# main.net
KiCad netlist of a schematic drawn in Altium Designer
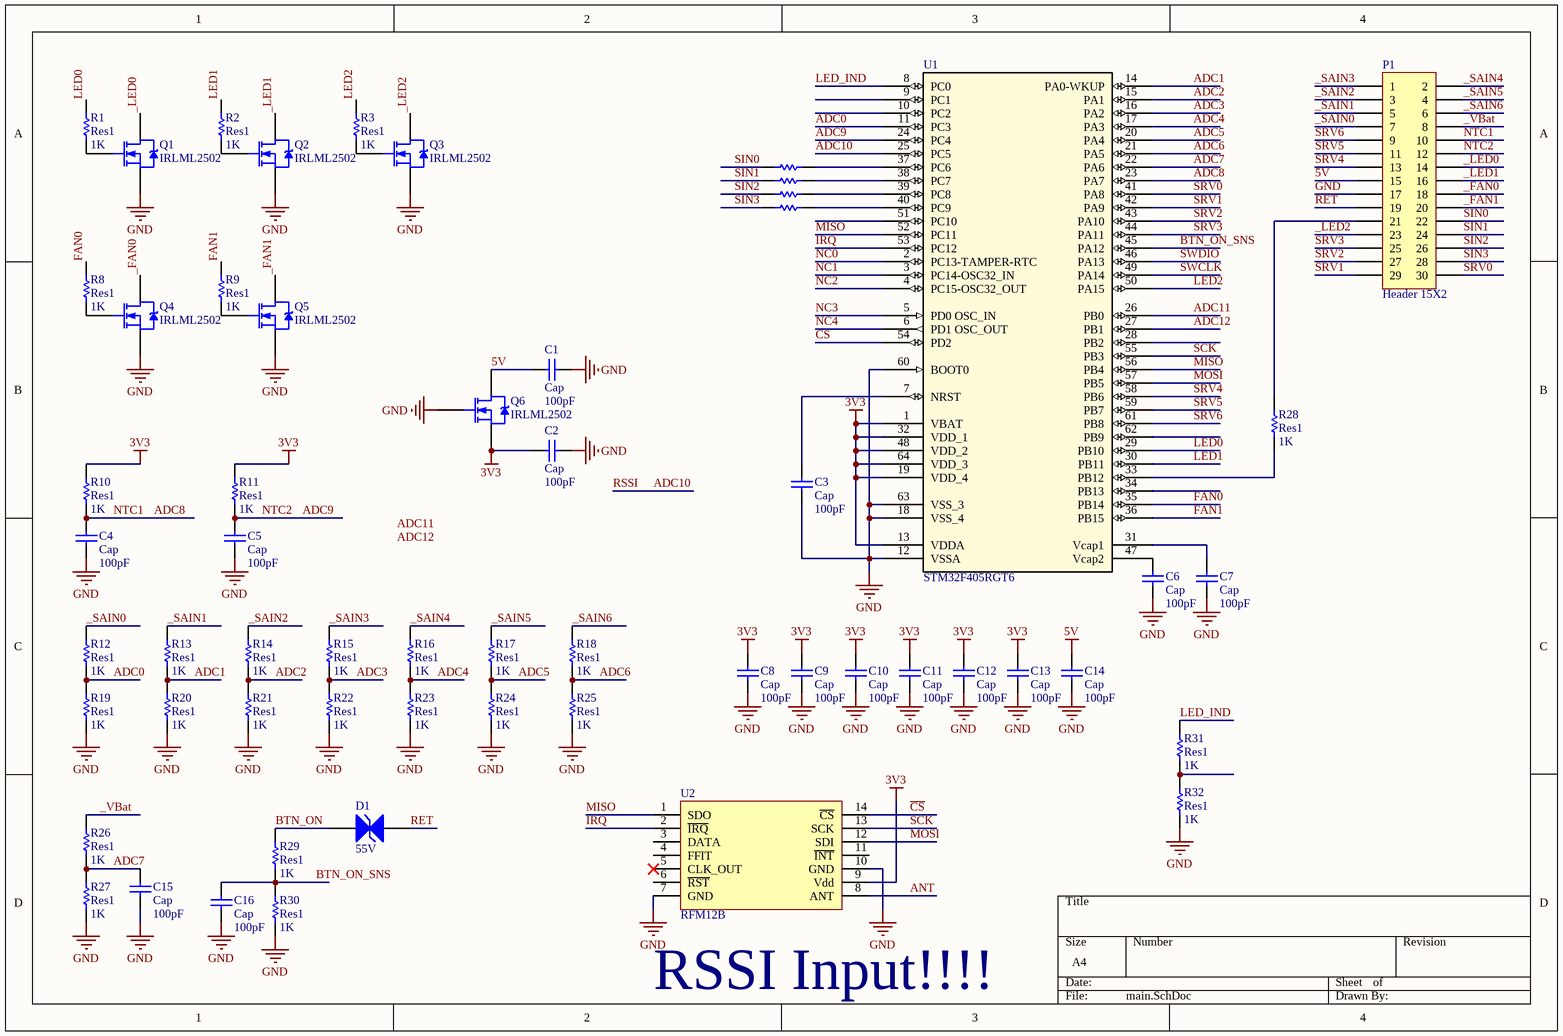
[diagram p0: main.SchDoc]

(export (version "E")
  (design (tool "Eeschema 10.0.6"))
  (components
    (comp (ref "C1")
      (value "Cap")
      (footprint "RC_1210_T1.8")
      (description "Capacitor")
      (fields (field (name "ALTIUM_VALUE") "100pF") (field (name "PUBLISHER") "Altium Limited"))
      (libsource (lib "Miscellaneous Devices") (part "Cap"))
    )
    (comp (ref "C2")
      (value "Cap")
      (footprint "RC_1210_T1.8")
      (description "Capacitor")
      (fields (field (name "ALTIUM_VALUE") "100pF") (field (name "PUBLISHER") "Altium Limited"))
      (libsource (lib "Miscellaneous Devices") (part "Cap"))
    )
    (comp (ref "C3")
      (value "Cap")
      (footprint "RC_0603")
      (description "Capacitor")
      (fields (field (name "ALTIUM_VALUE") "100pF") (field (name "PUBLISHER") "Altium Limited"))
      (libsource (lib "Miscellaneous Devices") (part "Cap"))
    )
    (comp (ref "C4")
      (value "Cap")
      (footprint "RC_0603")
      (description "Capacitor")
      (fields (field (name "ALTIUM_VALUE") "100pF") (field (name "PUBLISHER") "Altium Limited"))
      (libsource (lib "Miscellaneous Devices") (part "Cap"))
    )
    (comp (ref "C5")
      (value "Cap")
      (footprint "RC_0603")
      (description "Capacitor")
      (fields (field (name "ALTIUM_VALUE") "100pF") (field (name "PUBLISHER") "Altium Limited"))
      (libsource (lib "Miscellaneous Devices") (part "Cap"))
    )
    (comp (ref "C6")
      (value "Cap")
      (footprint "RC_0603")
      (description "Capacitor")
      (fields (field (name "ALTIUM_VALUE") "100pF") (field (name "PUBLISHER") "Altium Limited"))
      (libsource (lib "Miscellaneous Devices") (part "Cap"))
    )
    (comp (ref "C7")
      (value "Cap")
      (footprint "RC_0603")
      (description "Capacitor")
      (fields (field (name "ALTIUM_VALUE") "100pF") (field (name "PUBLISHER") "Altium Limited"))
      (libsource (lib "Miscellaneous Devices") (part "Cap"))
    )
    (comp (ref "C8")
      (value "Cap")
      (footprint "RC_0603")
      (description "Capacitor")
      (fields (field (name "ALTIUM_VALUE") "100pF") (field (name "PUBLISHER") "Altium Limited"))
      (libsource (lib "Miscellaneous Devices") (part "Cap"))
    )
    (comp (ref "C9")
      (value "Cap")
      (footprint "RC_0603")
      (description "Capacitor")
      (fields (field (name "ALTIUM_VALUE") "100pF") (field (name "PUBLISHER") "Altium Limited"))
      (libsource (lib "Miscellaneous Devices") (part "Cap"))
    )
    (comp (ref "C10")
      (value "Cap")
      (footprint "RC_0603")
      (description "Capacitor")
      (fields (field (name "ALTIUM_VALUE") "100pF") (field (name "PUBLISHER") "Altium Limited"))
      (libsource (lib "Miscellaneous Devices") (part "Cap"))
    )
    (comp (ref "C11")
      (value "Cap")
      (footprint "RC_0603")
      (description "Capacitor")
      (fields (field (name "ALTIUM_VALUE") "100pF") (field (name "PUBLISHER") "Altium Limited"))
      (libsource (lib "Miscellaneous Devices") (part "Cap"))
    )
    (comp (ref "C12")
      (value "Cap")
      (footprint "RC_0603")
      (description "Capacitor")
      (fields (field (name "ALTIUM_VALUE") "100pF") (field (name "PUBLISHER") "Altium Limited"))
      (libsource (lib "Miscellaneous Devices") (part "Cap"))
    )
    (comp (ref "C13")
      (value "Cap")
      (footprint "RC_0603")
      (description "Capacitor")
      (fields (field (name "ALTIUM_VALUE") "100pF") (field (name "PUBLISHER") "Altium Limited"))
      (libsource (lib "Miscellaneous Devices") (part "Cap"))
    )
    (comp (ref "C14")
      (value "Cap")
      (footprint "RC_0603")
      (description "Capacitor")
      (fields (field (name "ALTIUM_VALUE") "100pF") (field (name "PUBLISHER") "Altium Limited"))
      (libsource (lib "Miscellaneous Devices") (part "Cap"))
    )
    (comp (ref "C15")
      (value "Cap")
      (footprint "RC_0603")
      (description "Capacitor")
      (fields (field (name "ALTIUM_VALUE") "100pF") (field (name "PUBLISHER") "Altium Limited"))
      (libsource (lib "Miscellaneous Devices") (part "Cap"))
    )
    (comp (ref "C16")
      (value "Cap")
      (footprint "RC_0603")
      (description "Capacitor")
      (fields (field (name "ALTIUM_VALUE") "100pF") (field (name "PUBLISHER") "Altium Limited"))
      (libsource (lib "Miscellaneous Devices") (part "Cap"))
    )
    (comp (ref "D1")
      (value "55V")
      (footprint "RR_SOD-323")
      (description "DIODE TVS 55V")
      (fields (field (name "MANUFACTURER") "Diodes Incorporated"))
      (libsource (lib "RozumLibrary") (part "D55V0M1B2WS-7"))
    )
    (comp (ref "P1")
      (value "Header 15X2")
      (footprint "HDR2X15-2mm")
      (description "Header, 15-Pin, Dual row")
      (fields (field (name "PUBLISHER") "Altium Limited"))
      (libsource (lib "Miscellaneous Connectors") (part "Header 15X2"))
    )
    (comp (ref "Q1")
      (value "IRLML2502")
      (footprint "RR_SOT-23")
      (description "MOSFET N-CH 20V 4.2A SOT-23-3")
      (fields (field (name "MANUFACTURER") "Infineon Technologies"))
      (libsource (lib "RozumLibrary") (part "IRLML2502"))
    )
    (comp (ref "Q2")
      (value "IRLML2502")
      (footprint "RR_SOT-23")
      (description "MOSFET N-CH 20V 4.2A SOT-23-3")
      (fields (field (name "MANUFACTURER") "Infineon Technologies"))
      (libsource (lib "RozumLibrary") (part "IRLML2502"))
    )
    (comp (ref "Q3")
      (value "IRLML2502")
      (footprint "RR_SOT-23")
      (description "MOSFET N-CH 20V 4.2A SOT-23-3")
      (fields (field (name "MANUFACTURER") "Infineon Technologies"))
      (libsource (lib "RozumLibrary") (part "IRLML2502"))
    )
    (comp (ref "Q4")
      (value "IRLML2502")
      (footprint "RR_SOT-23")
      (description "MOSFET N-CH 20V 4.2A SOT-23-3")
      (fields (field (name "MANUFACTURER") "Infineon Technologies"))
      (libsource (lib "RozumLibrary") (part "IRLML2502"))
    )
    (comp (ref "Q5")
      (value "IRLML2502")
      (footprint "RR_SOT-23")
      (description "MOSFET N-CH 20V 4.2A SOT-23-3")
      (fields (field (name "MANUFACTURER") "Infineon Technologies"))
      (libsource (lib "RozumLibrary") (part "IRLML2502"))
    )
    (comp (ref "Q6")
      (value "IRLML2502")
      (footprint "RR_SOT-23")
      (description "MOSFET N-CH 20V 4.2A SOT-23-3")
      (fields (field (name "MANUFACTURER") "Infineon Technologies"))
      (libsource (lib "RozumLibrary") (part "IRLML2502"))
    )
    (comp (ref "R1")
      (value "Res1")
      (footprint "RR_0603")
      (description "Resistor")
      (fields (field (name "ALTIUM_VALUE") "1K") (field (name "PUBLISHER") "Altium Limited"))
      (libsource (lib "Miscellaneous Devices") (part "Res1"))
    )
    (comp (ref "R2")
      (value "Res1")
      (footprint "RR_0603")
      (description "Resistor")
      (fields (field (name "ALTIUM_VALUE") "1K") (field (name "PUBLISHER") "Altium Limited"))
      (libsource (lib "Miscellaneous Devices") (part "Res1"))
    )
    (comp (ref "R3")
      (value "Res1")
      (footprint "RR_0603")
      (description "Resistor")
      (fields (field (name "ALTIUM_VALUE") "1K") (field (name "PUBLISHER") "Altium Limited"))
      (libsource (lib "Miscellaneous Devices") (part "Res1"))
    )
    (comp (ref "R4")
      (value "Res1")
      (footprint "RR_0603")
      (description "Resistor")
      (fields (field (name "PUBLISHER") "Altium Limited"))
      (libsource (lib "Miscellaneous Devices") (part "Res1"))
    )
    (comp (ref "R5")
      (value "Res1")
      (footprint "RR_0603")
      (description "Resistor")
      (fields (field (name "PUBLISHER") "Altium Limited"))
      (libsource (lib "Miscellaneous Devices") (part "Res1"))
    )
    (comp (ref "R6")
      (value "Res1")
      (footprint "RR_0603")
      (description "Resistor")
      (fields (field (name "PUBLISHER") "Altium Limited"))
      (libsource (lib "Miscellaneous Devices") (part "Res1"))
    )
    (comp (ref "R7")
      (value "Res1")
      (footprint "RR_0603")
      (description "Resistor")
      (fields (field (name "PUBLISHER") "Altium Limited"))
      (libsource (lib "Miscellaneous Devices") (part "Res1"))
    )
    (comp (ref "R8")
      (value "Res1")
      (footprint "RR_0603")
      (description "Resistor")
      (fields (field (name "ALTIUM_VALUE") "1K") (field (name "PUBLISHER") "Altium Limited"))
      (libsource (lib "Miscellaneous Devices") (part "Res1"))
    )
    (comp (ref "R9")
      (value "Res1")
      (footprint "RR_0603")
      (description "Resistor")
      (fields (field (name "ALTIUM_VALUE") "1K") (field (name "PUBLISHER") "Altium Limited"))
      (libsource (lib "Miscellaneous Devices") (part "Res1"))
    )
    (comp (ref "R10")
      (value "Res1")
      (footprint "RR_0603")
      (description "Resistor")
      (fields (field (name "ALTIUM_VALUE") "1K") (field (name "PUBLISHER") "Altium Limited"))
      (libsource (lib "Miscellaneous Devices") (part "Res1"))
    )
    (comp (ref "R11")
      (value "Res1")
      (footprint "RR_0603")
      (description "Resistor")
      (fields (field (name "ALTIUM_VALUE") "1K") (field (name "PUBLISHER") "Altium Limited"))
      (libsource (lib "Miscellaneous Devices") (part "Res1"))
    )
    (comp (ref "R12")
      (value "Res1")
      (footprint "RR_0603")
      (description "Resistor")
      (fields (field (name "ALTIUM_VALUE") "1K") (field (name "PUBLISHER") "Altium Limited"))
      (libsource (lib "Miscellaneous Devices") (part "Res1"))
    )
    (comp (ref "R13")
      (value "Res1")
      (footprint "RR_0603")
      (description "Resistor")
      (fields (field (name "ALTIUM_VALUE") "1K") (field (name "PUBLISHER") "Altium Limited"))
      (libsource (lib "Miscellaneous Devices") (part "Res1"))
    )
    (comp (ref "R14")
      (value "Res1")
      (footprint "RR_0603")
      (description "Resistor")
      (fields (field (name "ALTIUM_VALUE") "1K") (field (name "PUBLISHER") "Altium Limited"))
      (libsource (lib "Miscellaneous Devices") (part "Res1"))
    )
    (comp (ref "R15")
      (value "Res1")
      (footprint "RR_0603")
      (description "Resistor")
      (fields (field (name "ALTIUM_VALUE") "1K") (field (name "PUBLISHER") "Altium Limited"))
      (libsource (lib "Miscellaneous Devices") (part "Res1"))
    )
    (comp (ref "R16")
      (value "Res1")
      (footprint "RR_0603")
      (description "Resistor")
      (fields (field (name "ALTIUM_VALUE") "1K") (field (name "PUBLISHER") "Altium Limited"))
      (libsource (lib "Miscellaneous Devices") (part "Res1"))
    )
    (comp (ref "R17")
      (value "Res1")
      (footprint "RR_0603")
      (description "Resistor")
      (fields (field (name "ALTIUM_VALUE") "1K") (field (name "PUBLISHER") "Altium Limited"))
      (libsource (lib "Miscellaneous Devices") (part "Res1"))
    )
    (comp (ref "R18")
      (value "Res1")
      (footprint "RR_0603")
      (description "Resistor")
      (fields (field (name "ALTIUM_VALUE") "1K") (field (name "PUBLISHER") "Altium Limited"))
      (libsource (lib "Miscellaneous Devices") (part "Res1"))
    )
    (comp (ref "R19")
      (value "Res1")
      (footprint "RR_0603")
      (description "Resistor")
      (fields (field (name "ALTIUM_VALUE") "1K") (field (name "PUBLISHER") "Altium Limited"))
      (libsource (lib "Miscellaneous Devices") (part "Res1"))
    )
    (comp (ref "R20")
      (value "Res1")
      (footprint "RR_0603")
      (description "Resistor")
      (fields (field (name "ALTIUM_VALUE") "1K") (field (name "PUBLISHER") "Altium Limited"))
      (libsource (lib "Miscellaneous Devices") (part "Res1"))
    )
    (comp (ref "R21")
      (value "Res1")
      (footprint "RR_0603")
      (description "Resistor")
      (fields (field (name "ALTIUM_VALUE") "1K") (field (name "PUBLISHER") "Altium Limited"))
      (libsource (lib "Miscellaneous Devices") (part "Res1"))
    )
    (comp (ref "R22")
      (value "Res1")
      (footprint "RR_0603")
      (description "Resistor")
      (fields (field (name "ALTIUM_VALUE") "1K") (field (name "PUBLISHER") "Altium Limited"))
      (libsource (lib "Miscellaneous Devices") (part "Res1"))
    )
    (comp (ref "R23")
      (value "Res1")
      (footprint "RR_0603")
      (description "Resistor")
      (fields (field (name "ALTIUM_VALUE") "1K") (field (name "PUBLISHER") "Altium Limited"))
      (libsource (lib "Miscellaneous Devices") (part "Res1"))
    )
    (comp (ref "R24")
      (value "Res1")
      (footprint "RR_0603")
      (description "Resistor")
      (fields (field (name "ALTIUM_VALUE") "1K") (field (name "PUBLISHER") "Altium Limited"))
      (libsource (lib "Miscellaneous Devices") (part "Res1"))
    )
    (comp (ref "R25")
      (value "Res1")
      (footprint "RR_0603")
      (description "Resistor")
      (fields (field (name "ALTIUM_VALUE") "1K") (field (name "PUBLISHER") "Altium Limited"))
      (libsource (lib "Miscellaneous Devices") (part "Res1"))
    )
    (comp (ref "R26")
      (value "Res1")
      (footprint "RR_0603")
      (description "Resistor")
      (fields (field (name "ALTIUM_VALUE") "1K") (field (name "PUBLISHER") "Altium Limited"))
      (libsource (lib "Miscellaneous Devices") (part "Res1"))
    )
    (comp (ref "R27")
      (value "Res1")
      (footprint "RR_0603")
      (description "Resistor")
      (fields (field (name "ALTIUM_VALUE") "1K") (field (name "PUBLISHER") "Altium Limited"))
      (libsource (lib "Miscellaneous Devices") (part "Res1"))
    )
    (comp (ref "R28")
      (value "Res1")
      (footprint "RR_0603")
      (description "Resistor")
      (fields (field (name "ALTIUM_VALUE") "1K") (field (name "PUBLISHER") "Altium Limited"))
      (libsource (lib "Miscellaneous Devices") (part "Res1"))
    )
    (comp (ref "R29")
      (value "Res1")
      (footprint "RR_0603")
      (description "Resistor")
      (fields (field (name "ALTIUM_VALUE") "1K") (field (name "PUBLISHER") "Altium Limited"))
      (libsource (lib "Miscellaneous Devices") (part "Res1"))
    )
    (comp (ref "R30")
      (value "Res1")
      (footprint "RR_0603")
      (description "Resistor")
      (fields (field (name "ALTIUM_VALUE") "1K") (field (name "PUBLISHER") "Altium Limited"))
      (libsource (lib "Miscellaneous Devices") (part "Res1"))
    )
    (comp (ref "R31")
      (value "Res1")
      (footprint "RR_0603")
      (description "Resistor")
      (fields (field (name "ALTIUM_VALUE") "1K") (field (name "PUBLISHER") "Altium Limited"))
      (libsource (lib "Miscellaneous Devices") (part "Res1"))
    )
    (comp (ref "R32")
      (value "Res1")
      (footprint "RR_0603")
      (description "Resistor")
      (fields (field (name "ALTIUM_VALUE") "1K") (field (name "PUBLISHER") "Altium Limited"))
      (libsource (lib "Miscellaneous Devices") (part "Res1"))
    )
    (comp (ref "U1")
      (value "STM32F405RGT6")
      (footprint "RR_LQFP-64")
      (description "MCU STM32F405RGT6")
      (fields (field (name "MANUFACTURER") "ST Microelectronics"))
      (libsource (lib "RozumLibrary") (part "STM32F405RGT6"))
    )
    (comp (ref "U2") (value "RFM12B") (libsource (lib "Schlib1") (part "Component_1")))
  )
  (nets
    (net (code "1") (name "/ADC0") (class "Default")
      (node (ref "R12") (pin "1") (pinfunction "1_1") (pintype "passive"))
      (node (ref "R19") (pin "2") (pinfunction "2_2") (pintype "passive"))
      (node (ref "U1") (pin "11") (pinfunction "PC3_11") (pintype "bidirectional"))
    )
    (net (code "2") (name "/ADC1") (class "Default")
      (node (ref "R13") (pin "1") (pinfunction "1_1") (pintype "passive"))
      (node (ref "R20") (pin "2") (pinfunction "2_2") (pintype "passive"))
      (node (ref "U1") (pin "14") (pinfunction "PA0-WKUP_14") (pintype "bidirectional"))
    )
    (net (code "3") (name "/ADC2") (class "Default")
      (node (ref "R14") (pin "1") (pinfunction "1_1") (pintype "passive"))
      (node (ref "R21") (pin "2") (pinfunction "2_2") (pintype "passive"))
      (node (ref "U1") (pin "15") (pinfunction "PA1_15") (pintype "bidirectional"))
    )
    (net (code "4") (name "/ADC3") (class "Default")
      (node (ref "R15") (pin "1") (pinfunction "1_1") (pintype "passive"))
      (node (ref "R22") (pin "2") (pinfunction "2_2") (pintype "passive"))
      (node (ref "U1") (pin "16") (pinfunction "PA2_16") (pintype "bidirectional"))
    )
    (net (code "5") (name "/ADC4") (class "Default")
      (node (ref "R16") (pin "1") (pinfunction "1_1") (pintype "passive"))
      (node (ref "R23") (pin "2") (pinfunction "2_2") (pintype "passive"))
      (node (ref "U1") (pin "17") (pinfunction "PA3_17") (pintype "bidirectional"))
    )
    (net (code "6") (name "/ADC5") (class "Default")
      (node (ref "R17") (pin "1") (pinfunction "1_1") (pintype "passive"))
      (node (ref "R24") (pin "2") (pinfunction "2_2") (pintype "passive"))
      (node (ref "U1") (pin "20") (pinfunction "PA4_20") (pintype "bidirectional"))
    )
    (net (code "7") (name "/ADC6") (class "Default")
      (node (ref "R18") (pin "1") (pinfunction "1_1") (pintype "passive"))
      (node (ref "R25") (pin "2") (pinfunction "2_2") (pintype "passive"))
      (node (ref "U1") (pin "21") (pinfunction "PA5_21") (pintype "bidirectional"))
    )
    (net (code "8") (name "/ADC7") (class "Default")
      (node (ref "C15") (pin "2") (pinfunction "2_2") (pintype "passive"))
      (node (ref "R26") (pin "1") (pinfunction "1_1") (pintype "passive"))
      (node (ref "R27") (pin "2") (pinfunction "2_2") (pintype "passive"))
      (node (ref "U1") (pin "22") (pinfunction "PA6_22") (pintype "bidirectional"))
    )
    (net (code "9") (name "/ADC8") (class "Default")
      (node (ref "C4") (pin "2") (pinfunction "2_2") (pintype "passive"))
      (node (ref "P1") (pin "10") (pinfunction "10_10") (pintype "passive"))
      (node (ref "R10") (pin "1") (pinfunction "1_1") (pintype "passive"))
      (node (ref "U1") (pin "23") (pinfunction "PA7_23") (pintype "bidirectional"))
    )
    (net (code "10") (name "/ADC9") (class "Default")
      (node (ref "C5") (pin "2") (pinfunction "2_2") (pintype "passive"))
      (node (ref "P1") (pin "12") (pinfunction "12_12") (pintype "passive"))
      (node (ref "R11") (pin "1") (pinfunction "1_1") (pintype "passive"))
      (node (ref "U1") (pin "24") (pinfunction "PC4_24") (pintype "bidirectional"))
    )
    (net (code "11") (name "/ADC10") (class "Default")
      (node (ref "U1") (pin "25") (pinfunction "PC5_25") (pintype "bidirectional"))
    )
    (net (code "12") (name "/ADC11") (class "Default")
      (node (ref "U1") (pin "26") (pinfunction "PB0_26") (pintype "bidirectional"))
    )
    (net (code "13") (name "/ADC12") (class "Default")
      (node (ref "U1") (pin "27") (pinfunction "PB1_27") (pintype "bidirectional"))
    )
    (net (code "14") (name "/ANT") (class "Default")
      (node (ref "U2") (pin "8") (pinfunction "ANT_8") (pintype "passive"))
    )
    (net (code "15") (name "/BTN_ON") (class "Default")
      (node (ref "D1") (pin "1") (pinfunction "A_1") (pintype "passive"))
      (node (ref "R29") (pin "2") (pinfunction "2_2") (pintype "passive"))
    )
    (net (code "16") (name "/BTN_ON_SNS") (class "Default")
      (node (ref "C16") (pin "2") (pinfunction "2_2") (pintype "passive"))
      (node (ref "R29") (pin "1") (pinfunction "1_1") (pintype "passive"))
      (node (ref "R30") (pin "2") (pinfunction "2_2") (pintype "passive"))
      (node (ref "U1") (pin "45") (pinfunction "PA12_45") (pintype "bidirectional"))
    )
    (net (code "17") (name "/FAN0") (class "Default")
      (node (ref "R8") (pin "2") (pinfunction "2_2") (pintype "passive"))
      (node (ref "U1") (pin "35") (pinfunction "PB14_35") (pintype "bidirectional"))
    )
    (net (code "18") (name "/FAN1") (class "Default")
      (node (ref "R9") (pin "2") (pinfunction "2_2") (pintype "passive"))
      (node (ref "U1") (pin "36") (pinfunction "PB15_36") (pintype "bidirectional"))
    )
    (net (code "19") (name "/LED0") (class "Default")
      (node (ref "R1") (pin "2") (pinfunction "2_2") (pintype "passive"))
      (node (ref "U1") (pin "29") (pinfunction "PB10_29") (pintype "bidirectional"))
    )
    (net (code "20") (name "/LED1") (class "Default")
      (node (ref "R2") (pin "2") (pinfunction "2_2") (pintype "passive"))
      (node (ref "U1") (pin "30") (pinfunction "PB11_30") (pintype "bidirectional"))
    )
    (net (code "21") (name "/LED2") (class "Default")
      (node (ref "R3") (pin "2") (pinfunction "2_2") (pintype "passive"))
      (node (ref "U1") (pin "50") (pinfunction "PA15_50") (pintype "bidirectional"))
    )
    (net (code "22") (name "/LED_IND") (class "Default")
      (node (ref "R31") (pin "2") (pinfunction "2_2") (pintype "passive"))
      (node (ref "U1") (pin "8") (pinfunction "PC0_8") (pintype "bidirectional"))
    )
    (net (code "23") (name "/MISO") (class "Default")
      (node (ref "U1") (pin "52") (pinfunction "PC11_52") (pintype "bidirectional"))
      (node (ref "U1") (pin "56") (pinfunction "PB4_56") (pintype "bidirectional"))
      (node (ref "U2") (pin "1") (pinfunction "SDO_1") (pintype "passive"))
    )
    (net (code "24") (name "/MOSI") (class "Default")
      (node (ref "U1") (pin "57") (pinfunction "PB5_57") (pintype "bidirectional"))
      (node (ref "U2") (pin "12") (pinfunction "SDI_12") (pintype "passive"))
    )
    (net (code "25") (name "/NC0") (class "Default")
      (node (ref "U1") (pin "2") (pinfunction "PC13-TAMPER-RTC_2") (pintype "bidirectional"))
    )
    (net (code "26") (name "/NC1") (class "Default")
      (node (ref "U1") (pin "3") (pinfunction "PC14-OSC32_IN_3") (pintype "bidirectional"))
    )
    (net (code "27") (name "/NC2") (class "Default")
      (node (ref "U1") (pin "4") (pinfunction "PC15-OSC32_OUT_4") (pintype "bidirectional"))
    )
    (net (code "28") (name "/NC3") (class "Default")
      (node (ref "U1") (pin "5") (pinfunction "PD0_OSC_IN_5") (pintype "input"))
    )
    (net (code "29") (name "/NC4") (class "Default")
      (node (ref "U1") (pin "6") (pinfunction "PD1_OSC_OUT_6") (pintype "output"))
    )
    (net (code "30") (name "/RET") (class "Default")
      (node (ref "D1") (pin "2") (pinfunction "A_2") (pintype "passive"))
      (node (ref "P1") (pin "19") (pinfunction "19_19") (pintype "passive"))
    )
    (net (code "31") (name "/SCK") (class "Default")
      (node (ref "U1") (pin "55") (pinfunction "PB3_55") (pintype "bidirectional"))
      (node (ref "U2") (pin "13") (pinfunction "SCK_13") (pintype "passive"))
    )
    (net (code "32") (name "/SIN0") (class "Default")
      (node (ref "P1") (pin "22") (pinfunction "22_22") (pintype "passive"))
      (node (ref "R4") (pin "2") (pinfunction "2_2") (pintype "passive"))
    )
    (net (code "33") (name "/SIN1") (class "Default")
      (node (ref "P1") (pin "24") (pinfunction "24_24") (pintype "passive"))
      (node (ref "R5") (pin "2") (pinfunction "2_2") (pintype "passive"))
    )
    (net (code "34") (name "/SIN2") (class "Default")
      (node (ref "P1") (pin "26") (pinfunction "26_26") (pintype "passive"))
      (node (ref "R6") (pin "2") (pinfunction "2_2") (pintype "passive"))
    )
    (net (code "35") (name "/SIN3") (class "Default")
      (node (ref "P1") (pin "28") (pinfunction "28_28") (pintype "passive"))
      (node (ref "R7") (pin "2") (pinfunction "2_2") (pintype "passive"))
    )
    (net (code "36") (name "/SRV0") (class "Default")
      (node (ref "P1") (pin "30") (pinfunction "30_30") (pintype "passive"))
      (node (ref "U1") (pin "41") (pinfunction "PA8_41") (pintype "bidirectional"))
    )
    (net (code "37") (name "/SRV1") (class "Default")
      (node (ref "P1") (pin "29") (pinfunction "29_29") (pintype "passive"))
      (node (ref "U1") (pin "42") (pinfunction "PA9_42") (pintype "bidirectional"))
    )
    (net (code "38") (name "/SRV2") (class "Default")
      (node (ref "P1") (pin "27") (pinfunction "27_27") (pintype "passive"))
      (node (ref "U1") (pin "43") (pinfunction "PA10_43") (pintype "bidirectional"))
    )
    (net (code "39") (name "/SRV3") (class "Default")
      (node (ref "P1") (pin "25") (pinfunction "25_25") (pintype "passive"))
      (node (ref "U1") (pin "44") (pinfunction "PA11_44") (pintype "bidirectional"))
    )
    (net (code "40") (name "/SRV4") (class "Default")
      (node (ref "P1") (pin "13") (pinfunction "13_13") (pintype "passive"))
      (node (ref "U1") (pin "58") (pinfunction "PB6_58") (pintype "bidirectional"))
    )
    (net (code "41") (name "/SRV5") (class "Default")
      (node (ref "P1") (pin "11") (pinfunction "11_11") (pintype "passive"))
      (node (ref "U1") (pin "59") (pinfunction "PB7_59") (pintype "bidirectional"))
    )
    (net (code "42") (name "/SRV6") (class "Default")
      (node (ref "P1") (pin "9") (pinfunction "9_9") (pintype "passive"))
      (node (ref "U1") (pin "61") (pinfunction "PB8_61") (pintype "bidirectional"))
    )
    (net (code "43") (name "/SWCLK") (class "Default")
      (node (ref "U1") (pin "49") (pinfunction "PA14_49") (pintype "bidirectional"))
    )
    (net (code "44") (name "/SWDIO") (class "Default")
      (node (ref "U1") (pin "46") (pinfunction "PA13_46") (pintype "bidirectional"))
    )
    (net (code "45") (name "/_FAN0") (class "Default")
      (node (ref "P1") (pin "18") (pinfunction "18_18") (pintype "passive"))
      (node (ref "Q4") (pin "3") (pinfunction "D_3") (pintype "passive"))
    )
    (net (code "46") (name "/_FAN1") (class "Default")
      (node (ref "P1") (pin "20") (pinfunction "20_20") (pintype "passive"))
      (node (ref "Q5") (pin "3") (pinfunction "D_3") (pintype "passive"))
    )
    (net (code "47") (name "/_LED0") (class "Default")
      (node (ref "P1") (pin "14") (pinfunction "14_14") (pintype "passive"))
      (node (ref "Q1") (pin "3") (pinfunction "D_3") (pintype "passive"))
    )
    (net (code "48") (name "/_LED1") (class "Default")
      (node (ref "P1") (pin "16") (pinfunction "16_16") (pintype "passive"))
      (node (ref "Q2") (pin "3") (pinfunction "D_3") (pintype "passive"))
    )
    (net (code "49") (name "/_LED2") (class "Default")
      (node (ref "P1") (pin "23") (pinfunction "23_23") (pintype "passive"))
      (node (ref "Q3") (pin "3") (pinfunction "D_3") (pintype "passive"))
    )
    (net (code "50") (name "/_SAIN0") (class "Default")
      (node (ref "P1") (pin "7") (pinfunction "7_7") (pintype "passive"))
      (node (ref "R12") (pin "2") (pinfunction "2_2") (pintype "passive"))
    )
    (net (code "51") (name "/_SAIN1") (class "Default")
      (node (ref "P1") (pin "5") (pinfunction "5_5") (pintype "passive"))
      (node (ref "R13") (pin "2") (pinfunction "2_2") (pintype "passive"))
    )
    (net (code "52") (name "/_SAIN2") (class "Default")
      (node (ref "P1") (pin "3") (pinfunction "3_3") (pintype "passive"))
      (node (ref "R14") (pin "2") (pinfunction "2_2") (pintype "passive"))
    )
    (net (code "53") (name "/_SAIN3") (class "Default")
      (node (ref "P1") (pin "1") (pinfunction "1_1") (pintype "passive"))
      (node (ref "R15") (pin "2") (pinfunction "2_2") (pintype "passive"))
    )
    (net (code "54") (name "/_SAIN4") (class "Default")
      (node (ref "P1") (pin "2") (pinfunction "2_2") (pintype "passive"))
      (node (ref "R16") (pin "2") (pinfunction "2_2") (pintype "passive"))
    )
    (net (code "55") (name "/_SAIN5") (class "Default")
      (node (ref "P1") (pin "4") (pinfunction "4_4") (pintype "passive"))
      (node (ref "R17") (pin "2") (pinfunction "2_2") (pintype "passive"))
    )
    (net (code "56") (name "/_SAIN6") (class "Default")
      (node (ref "P1") (pin "6") (pinfunction "6_6") (pintype "passive"))
      (node (ref "R18") (pin "2") (pinfunction "2_2") (pintype "passive"))
    )
    (net (code "57") (name "/_VBat") (class "Default")
      (node (ref "P1") (pin "8") (pinfunction "8_8") (pintype "passive"))
      (node (ref "R26") (pin "2") (pinfunction "2_2") (pintype "passive"))
    )
    (net (code "58") (name "/~{CS}") (class "Default")
      (node (ref "U1") (pin "54") (pinfunction "PD2_54") (pintype "bidirectional"))
      (node (ref "U2") (pin "14") (pinfunction "~{CS}_14") (pintype "passive"))
    )
    (net (code "59") (name "/~{IRQ}") (class "Default")
      (node (ref "U1") (pin "53") (pinfunction "PC12_53") (pintype "bidirectional"))
      (node (ref "U2") (pin "2") (pinfunction "~{IRQ}_2") (pintype "passive"))
    )
    (net (code "60") (name "3V3") (class "Default")
      (node (ref "C10") (pin "2") (pinfunction "2_2") (pintype "passive"))
      (node (ref "C11") (pin "2") (pinfunction "2_2") (pintype "passive"))
      (node (ref "C12") (pin "2") (pinfunction "2_2") (pintype "passive"))
      (node (ref "C13") (pin "2") (pinfunction "2_2") (pintype "passive"))
      (node (ref "C2") (pin "2") (pinfunction "2_2") (pintype "passive"))
      (node (ref "C8") (pin "2") (pinfunction "2_2") (pintype "passive"))
      (node (ref "C9") (pin "2") (pinfunction "2_2") (pintype "passive"))
      (node (ref "Q6") (pin "2") (pinfunction "S_2") (pintype "passive"))
      (node (ref "R10") (pin "2") (pinfunction "2_2") (pintype "passive"))
      (node (ref "R11") (pin "2") (pinfunction "2_2") (pintype "passive"))
      (node (ref "U1") (pin "1") (pinfunction "VBAT_1") (pintype "power_in"))
      (node (ref "U1") (pin "13") (pinfunction "VDDA_13") (pintype "power_in"))
      (node (ref "U1") (pin "19") (pinfunction "VDD_4_19") (pintype "power_in"))
      (node (ref "U1") (pin "32") (pinfunction "VDD_1_32") (pintype "power_in"))
      (node (ref "U1") (pin "48") (pinfunction "VDD_2_48") (pintype "power_in"))
      (node (ref "U1") (pin "64") (pinfunction "VDD_3_64") (pintype "power_in"))
      (node (ref "U2") (pin "9") (pinfunction "Vdd_9") (pintype "passive"))
    )
    (net (code "61") (name "5V") (class "Default")
      (node (ref "C1") (pin "2") (pinfunction "2_2") (pintype "passive"))
      (node (ref "C14") (pin "2") (pinfunction "2_2") (pintype "passive"))
      (node (ref "P1") (pin "15") (pinfunction "15_15") (pintype "passive"))
      (node (ref "Q6") (pin "3") (pinfunction "D_3") (pintype "passive"))
    )
    (net (code "62") (name "GND") (class "Default")
      (node (ref "C1") (pin "1") (pinfunction "1_1") (pintype "passive"))
      (node (ref "C10") (pin "1") (pinfunction "1_1") (pintype "passive"))
      (node (ref "C11") (pin "1") (pinfunction "1_1") (pintype "passive"))
      (node (ref "C12") (pin "1") (pinfunction "1_1") (pintype "passive"))
      (node (ref "C13") (pin "1") (pinfunction "1_1") (pintype "passive"))
      (node (ref "C14") (pin "1") (pinfunction "1_1") (pintype "passive"))
      (node (ref "C15") (pin "1") (pinfunction "1_1") (pintype "passive"))
      (node (ref "C16") (pin "1") (pinfunction "1_1") (pintype "passive"))
      (node (ref "C2") (pin "1") (pinfunction "1_1") (pintype "passive"))
      (node (ref "C3") (pin "1") (pinfunction "1_1") (pintype "passive"))
      (node (ref "C4") (pin "1") (pinfunction "1_1") (pintype "passive"))
      (node (ref "C5") (pin "1") (pinfunction "1_1") (pintype "passive"))
      (node (ref "C6") (pin "1") (pinfunction "1_1") (pintype "passive"))
      (node (ref "C7") (pin "1") (pinfunction "1_1") (pintype "passive"))
      (node (ref "C8") (pin "1") (pinfunction "1_1") (pintype "passive"))
      (node (ref "C9") (pin "1") (pinfunction "1_1") (pintype "passive"))
      (node (ref "P1") (pin "17") (pinfunction "17_17") (pintype "passive"))
      (node (ref "Q1") (pin "2") (pinfunction "S_2") (pintype "passive"))
      (node (ref "Q2") (pin "2") (pinfunction "S_2") (pintype "passive"))
      (node (ref "Q3") (pin "2") (pinfunction "S_2") (pintype "passive"))
      (node (ref "Q4") (pin "2") (pinfunction "S_2") (pintype "passive"))
      (node (ref "Q5") (pin "2") (pinfunction "S_2") (pintype "passive"))
      (node (ref "Q6") (pin "1") (pinfunction "G_1") (pintype "passive"))
      (node (ref "R19") (pin "1") (pinfunction "1_1") (pintype "passive"))
      (node (ref "R20") (pin "1") (pinfunction "1_1") (pintype "passive"))
      (node (ref "R21") (pin "1") (pinfunction "1_1") (pintype "passive"))
      (node (ref "R22") (pin "1") (pinfunction "1_1") (pintype "passive"))
      (node (ref "R23") (pin "1") (pinfunction "1_1") (pintype "passive"))
      (node (ref "R24") (pin "1") (pinfunction "1_1") (pintype "passive"))
      (node (ref "R25") (pin "1") (pinfunction "1_1") (pintype "passive"))
      (node (ref "R27") (pin "1") (pinfunction "1_1") (pintype "passive"))
      (node (ref "R30") (pin "1") (pinfunction "1_1") (pintype "passive"))
      (node (ref "R32") (pin "1") (pinfunction "1_1") (pintype "passive"))
      (node (ref "U1") (pin "12") (pinfunction "VSSA_12") (pintype "power_in"))
      (node (ref "U1") (pin "18") (pinfunction "VSS_4_18") (pintype "power_in"))
      (node (ref "U1") (pin "60") (pinfunction "BOOT0_60") (pintype "input"))
      (node (ref "U1") (pin "63") (pinfunction "VSS_3_63") (pintype "power_in"))
      (node (ref "U2") (pin "10") (pinfunction "GND_10") (pintype "passive"))
      (node (ref "U2") (pin "7") (pinfunction "GND_7") (pintype "passive"))
    )
    (net (code "63") (name "Net-(P1-Pad21)") (class "Default")
      (node (ref "P1") (pin "21") (pinfunction "21_21") (pintype "passive"))
      (node (ref "R28") (pin "2") (pinfunction "2_2") (pintype "passive"))
    )
    (net (code "64") (name "Net-(Q1-G)") (class "Default")
      (node (ref "Q1") (pin "1") (pinfunction "G_1") (pintype "passive"))
      (node (ref "R1") (pin "1") (pinfunction "1_1") (pintype "passive"))
    )
    (net (code "65") (name "Net-(Q2-G)") (class "Default")
      (node (ref "Q2") (pin "1") (pinfunction "G_1") (pintype "passive"))
      (node (ref "R2") (pin "1") (pinfunction "1_1") (pintype "passive"))
    )
    (net (code "66") (name "Net-(Q3-G)") (class "Default")
      (node (ref "Q3") (pin "1") (pinfunction "G_1") (pintype "passive"))
      (node (ref "R3") (pin "1") (pinfunction "1_1") (pintype "passive"))
    )
    (net (code "67") (name "Net-(Q4-G)") (class "Default")
      (node (ref "Q4") (pin "1") (pinfunction "G_1") (pintype "passive"))
      (node (ref "R8") (pin "1") (pinfunction "1_1") (pintype "passive"))
    )
    (net (code "68") (name "Net-(Q5-G)") (class "Default")
      (node (ref "Q5") (pin "1") (pinfunction "G_1") (pintype "passive"))
      (node (ref "R9") (pin "1") (pinfunction "1_1") (pintype "passive"))
    )
    (net (code "69") (name "Net-(R31-Pad1)") (class "Default")
      (node (ref "R31") (pin "1") (pinfunction "1_1") (pintype "passive"))
      (node (ref "R32") (pin "2") (pinfunction "2_2") (pintype "passive"))
    )
    (net (code "70") (name "Net-(U1-NRST)") (class "Default")
      (node (ref "C3") (pin "2") (pinfunction "2_2") (pintype "passive"))
      (node (ref "U1") (pin "7") (pinfunction "NRST_7") (pintype "bidirectional"))
    )
    (net (code "71") (name "Net-(U1-PB12)") (class "Default")
      (node (ref "R28") (pin "1") (pinfunction "1_1") (pintype "passive"))
      (node (ref "U1") (pin "33") (pinfunction "PB12_33") (pintype "bidirectional"))
    )
    (net (code "72") (name "Net-(U1-PC6)") (class "Default")
      (node (ref "R4") (pin "1") (pinfunction "1_1") (pintype "passive"))
      (node (ref "U1") (pin "37") (pinfunction "PC6_37") (pintype "bidirectional"))
    )
    (net (code "73") (name "Net-(U1-PC7)") (class "Default")
      (node (ref "R5") (pin "1") (pinfunction "1_1") (pintype "passive"))
      (node (ref "U1") (pin "38") (pinfunction "PC7_38") (pintype "bidirectional"))
    )
    (net (code "74") (name "Net-(U1-PC8)") (class "Default")
      (node (ref "R6") (pin "1") (pinfunction "1_1") (pintype "passive"))
      (node (ref "U1") (pin "39") (pinfunction "PC8_39") (pintype "bidirectional"))
    )
    (net (code "75") (name "Net-(U1-PC9)") (class "Default")
      (node (ref "R7") (pin "1") (pinfunction "1_1") (pintype "passive"))
      (node (ref "U1") (pin "40") (pinfunction "PC9_40") (pintype "bidirectional"))
    )
    (net (code "76") (name "Net-(U1-Vcap1)") (class "Default")
      (node (ref "C7") (pin "2") (pinfunction "2_2") (pintype "passive"))
      (node (ref "U1") (pin "31") (pinfunction "Vcap1_31") (pintype "power_in"))
    )
    (net (code "77") (name "Net-(U1-Vcap2)") (class "Default")
      (node (ref "C6") (pin "2") (pinfunction "2_2") (pintype "passive"))
      (node (ref "U1") (pin "47") (pinfunction "Vcap2_47") (pintype "power_in"))
    )
    (net (code "78") (name "unconnected-(U1-PB2-Pad28)") (class "Default")
      (node (ref "U1") (pin "28") (pinfunction "PB2_28") (pintype "bidirectional"))
    )
    (net (code "79") (name "unconnected-(U1-PB9-Pad62)") (class "Default")
      (node (ref "U1") (pin "62") (pinfunction "PB9_62") (pintype "bidirectional"))
    )
    (net (code "80") (name "unconnected-(U1-PB13-Pad34)") (class "Default")
      (node (ref "U1") (pin "34") (pinfunction "PB13_34") (pintype "bidirectional"))
    )
    (net (code "81") (name "unconnected-(U1-PC1-Pad9)") (class "Default")
      (node (ref "U1") (pin "9") (pinfunction "PC1_9") (pintype "bidirectional"))
    )
    (net (code "82") (name "unconnected-(U1-PC2-Pad10)") (class "Default")
      (node (ref "U1") (pin "10") (pinfunction "PC2_10") (pintype "bidirectional"))
    )
    (net (code "83") (name "unconnected-(U1-PC10-Pad51)") (class "Default")
      (node (ref "U1") (pin "51") (pinfunction "PC10_51") (pintype "bidirectional"))
    )
    (net (code "84") (name "unconnected-(U2-CLK_OUT-Pad5)") (class "Default")
      (node (ref "U2") (pin "5") (pinfunction "CLK_OUT_5") (pintype "passive+no_connect"))
    )
    (net (code "85") (name "unconnected-(U2-DATA-Pad3)") (class "Default")
      (node (ref "U2") (pin "3") (pinfunction "DATA_3") (pintype "passive"))
    )
    (net (code "86") (name "unconnected-(U2-FFIT-Pad4)") (class "Default")
      (node (ref "U2") (pin "4") (pinfunction "FFIT_4") (pintype "passive"))
    )
    (net (code "87") (name "unconnected-(U2-~{INT}-Pad11)") (class "Default")
      (node (ref "U2") (pin "11") (pinfunction "~{INT}_11") (pintype "passive"))
    )
    (net (code "88") (name "unconnected-(U2-~{RST}-Pad6)") (class "Default")
      (node (ref "U2") (pin "6") (pinfunction "~{RST}_6") (pintype "passive"))
    )
  )
)
